# RPL_POWER_3V3.net
KiCad netlist of a schematic drawn in Altium Designer
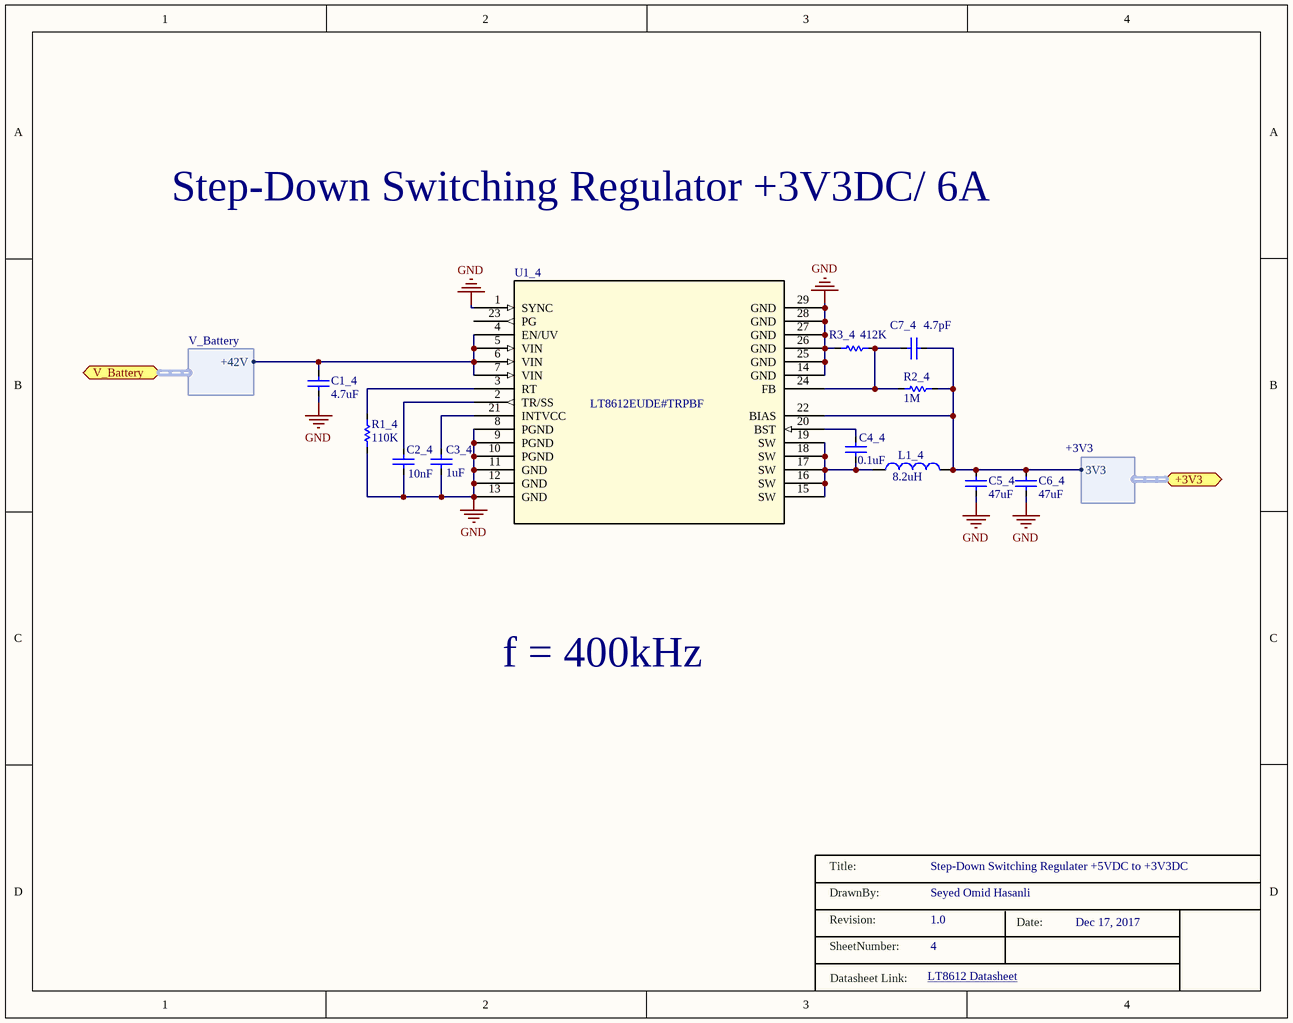
[diagram p0: RPL_POWER_3V3.SchDoc]

(export (version "E")
  (design (tool "Eeschema 10.0.6"))
  (components
    (comp (ref "C1_4")
      (value "4.7uF")
      (footprint "C0805C475K9RACAUTO")
      (fields (field (name "Comment") "Cap"))
      (libsource (lib "Generic_Library") (part "Cap"))
    )
    (comp (ref "C2_4")
      (value "10nF")
      (footprint "C0805C475K9RACAUTO")
      (fields (field (name "Comment") "Cap"))
      (libsource (lib "Generic_Library") (part "Cap"))
    )
    (comp (ref "C3_4")
      (value "1uF")
      (footprint "C0805C475K9RACAUTO")
      (fields (field (name "Comment") "Cap"))
      (libsource (lib "Generic_Library") (part "Cap"))
    )
    (comp (ref "C4_4")
      (value "0.1uF")
      (footprint "C0805C475K9RACAUTO")
      (fields (field (name "Comment") "Cap"))
      (libsource (lib "Generic_Library") (part "Cap"))
    )
    (comp (ref "C5_4")
      (value "47uF")
      (footprint "C0805C475K9RACAUTO")
      (fields (field (name "Comment") "Cap"))
      (libsource (lib "Generic_Library") (part "Cap"))
    )
    (comp (ref "C6_4")
      (value "47uF")
      (footprint "C0805C475K9RACAUTO")
      (fields (field (name "Comment") "Cap"))
      (libsource (lib "Generic_Library") (part "Cap"))
    )
    (comp (ref "C7_4")
      (value "4.7pF")
      (footprint "C0805C475K9RACAUTO")
      (fields (field (name "Comment") "Cap"))
      (libsource (lib "Generic_Library") (part "Cap"))
    )
    (comp (ref "L1_4")
      (value "8.2uH")
      (footprint "74404063082")
      (fields (field (name "Comment") "Inductor"))
      (libsource (lib "Generic_Library") (part "Inductor"))
    )
    (comp (ref "R1_4")
      (value "110K")
      (footprint "SMD Resistors:RES 0805")
      (fields (field (name "Comment") "Res"))
      (libsource (lib "Generic_Library") (part "Res"))
    )
    (comp (ref "R2_4")
      (value "1M")
      (footprint "SMD Resistors:RES 0805")
      (fields (field (name "Comment") "Res"))
      (libsource (lib "Generic_Library") (part "Res"))
    )
    (comp (ref "R3_4")
      (value "412K")
      (footprint "SMD Resistors:RES 0805")
      (fields (field (name "Comment") "Res"))
      (libsource (lib "Generic_Library") (part "Res"))
    )
    (comp (ref "U1_4")
      (value "LT8612EUDE#TRPBF")
      (footprint "QFN-28_UDE-M")
      (description "Imported")
      (fields (field (name "MANUFACTURER_PART_NUMBER") "lt8612eude#trpbf"))
      (libsource (lib "Generic_Library") (part "LT8612EUDE#TRPBF"))
    )
  )
  (nets
    (net (code "5") (name "GND") (class "Default")
      (node (ref "C1_4") (pin "1") (pinfunction "1_1") (pintype "passive"))
      (node (ref "C2_4") (pin "1") (pinfunction "1_1") (pintype "passive"))
      (node (ref "C3_4") (pin "1") (pinfunction "1_1") (pintype "passive"))
      (node (ref "C5_4") (pin "1") (pinfunction "1_1") (pintype "passive"))
      (node (ref "C6_4") (pin "1") (pinfunction "1_1") (pintype "passive"))
      (node (ref "R1_4") (pin "1") (pinfunction "1_1") (pintype "passive"))
      (node (ref "R3_4") (pin "2") (pinfunction "2_2") (pintype "passive"))
      (node (ref "U1_4") (pin "1") (pinfunction "SYNC_1") (pintype "input"))
      (node (ref "U1_4") (pin "10") (pinfunction "PGND_10") (pintype "power_in"))
      (node (ref "U1_4") (pin "11") (pinfunction "GND_11") (pintype "power_in"))
      (node (ref "U1_4") (pin "12") (pinfunction "GND_12") (pintype "power_in"))
      (node (ref "U1_4") (pin "13") (pinfunction "GND_13") (pintype "power_in"))
      (node (ref "U1_4") (pin "14") (pinfunction "GND_14") (pintype "power_in"))
      (node (ref "U1_4") (pin "25") (pinfunction "GND_25") (pintype "power_in"))
      (node (ref "U1_4") (pin "26") (pinfunction "GND_26") (pintype "power_in"))
      (node (ref "U1_4") (pin "27") (pinfunction "GND_27") (pintype "power_in"))
      (node (ref "U1_4") (pin "28") (pinfunction "GND_28") (pintype "power_in"))
      (node (ref "U1_4") (pin "29") (pinfunction "GND_29") (pintype "power_in"))
      (node (ref "U1_4") (pin "8") (pinfunction "PGND_8") (pintype "power_in"))
      (node (ref "U1_4") (pin "9") (pinfunction "PGND_9") (pintype "power_in"))
    )
    (net (code "6") (name "Net-(C4_4-Pad1)") (class "Default")
      (node (ref "C4_4") (pin "1") (pinfunction "1_1") (pintype "passive"))
      (node (ref "L1_4") (pin "1") (pinfunction "1_1") (pintype "passive"))
      (node (ref "U1_4") (pin "15") (pinfunction "SW_15") (pintype "passive"))
      (node (ref "U1_4") (pin "16") (pinfunction "SW_16") (pintype "passive"))
      (node (ref "U1_4") (pin "17") (pinfunction "SW_17") (pintype "passive"))
      (node (ref "U1_4") (pin "18") (pinfunction "SW_18") (pintype "passive"))
      (node (ref "U1_4") (pin "19") (pinfunction "SW_19") (pintype "passive"))
    )
    (net (code "7") (name "Net-(U1_4-BIAS)") (class "Default")
      (node (ref "C5_4") (pin "2") (pinfunction "2_2") (pintype "passive"))
      (node (ref "C6_4") (pin "2") (pinfunction "2_2") (pintype "passive"))
      (node (ref "C7_4") (pin "2") (pinfunction "2_2") (pintype "passive"))
      (node (ref "L1_4") (pin "2") (pinfunction "2_2") (pintype "passive"))
      (node (ref "R2_4") (pin "2") (pinfunction "2_2") (pintype "passive"))
      (node (ref "U1_4") (pin "22") (pinfunction "BIAS_22") (pintype "passive"))
    )
    (net (code "8") (name "Net-(U1_4-BST)") (class "Default")
      (node (ref "C4_4") (pin "2") (pinfunction "2_2") (pintype "passive"))
      (node (ref "U1_4") (pin "20") (pinfunction "BST_20") (pintype "input"))
    )
    (net (code "9") (name "Net-(U1_4-EN{slash}UV)") (class "Default")
      (node (ref "C1_4") (pin "2") (pinfunction "2_2") (pintype "passive"))
      (node (ref "U1_4") (pin "4") (pinfunction "EN/UV_4") (pintype "passive"))
      (node (ref "U1_4") (pin "5") (pinfunction "VIN_5") (pintype "input"))
      (node (ref "U1_4") (pin "6") (pinfunction "VIN_6") (pintype "input"))
      (node (ref "U1_4") (pin "7") (pinfunction "VIN_7") (pintype "input"))
    )
    (net (code "10") (name "Net-(U1_4-FB)") (class "Default")
      (node (ref "C7_4") (pin "1") (pinfunction "1_1") (pintype "passive"))
      (node (ref "R2_4") (pin "1") (pinfunction "1_1") (pintype "passive"))
      (node (ref "R3_4") (pin "1") (pinfunction "1_1") (pintype "passive"))
      (node (ref "U1_4") (pin "24") (pinfunction "FB_24") (pintype "passive"))
    )
    (net (code "11") (name "Net-(U1_4-INTVCC)") (class "Default")
      (node (ref "C3_4") (pin "2") (pinfunction "2_2") (pintype "passive"))
      (node (ref "U1_4") (pin "21") (pinfunction "INTVCC_21") (pintype "passive"))
    )
    (net (code "12") (name "Net-(U1_4-RT)") (class "Default")
      (node (ref "R1_4") (pin "2") (pinfunction "2_2") (pintype "passive"))
      (node (ref "U1_4") (pin "3") (pinfunction "RT_3") (pintype "passive"))
    )
    (net (code "13") (name "Net-(U1_4-TR{slash}SS)") (class "Default")
      (node (ref "C2_4") (pin "2") (pinfunction "2_2") (pintype "passive"))
      (node (ref "U1_4") (pin "2") (pinfunction "TR/SS_2") (pintype "output"))
    )
    (net (code "14") (name "unconnected-(U1_4-PG-Pad23)") (class "Default")
      (node (ref "U1_4") (pin "23") (pinfunction "PG_23") (pintype "output"))
    )
  )
)
